# mm_controller_v1.net
KiCad netlist of a schematic drawn in EAGLE
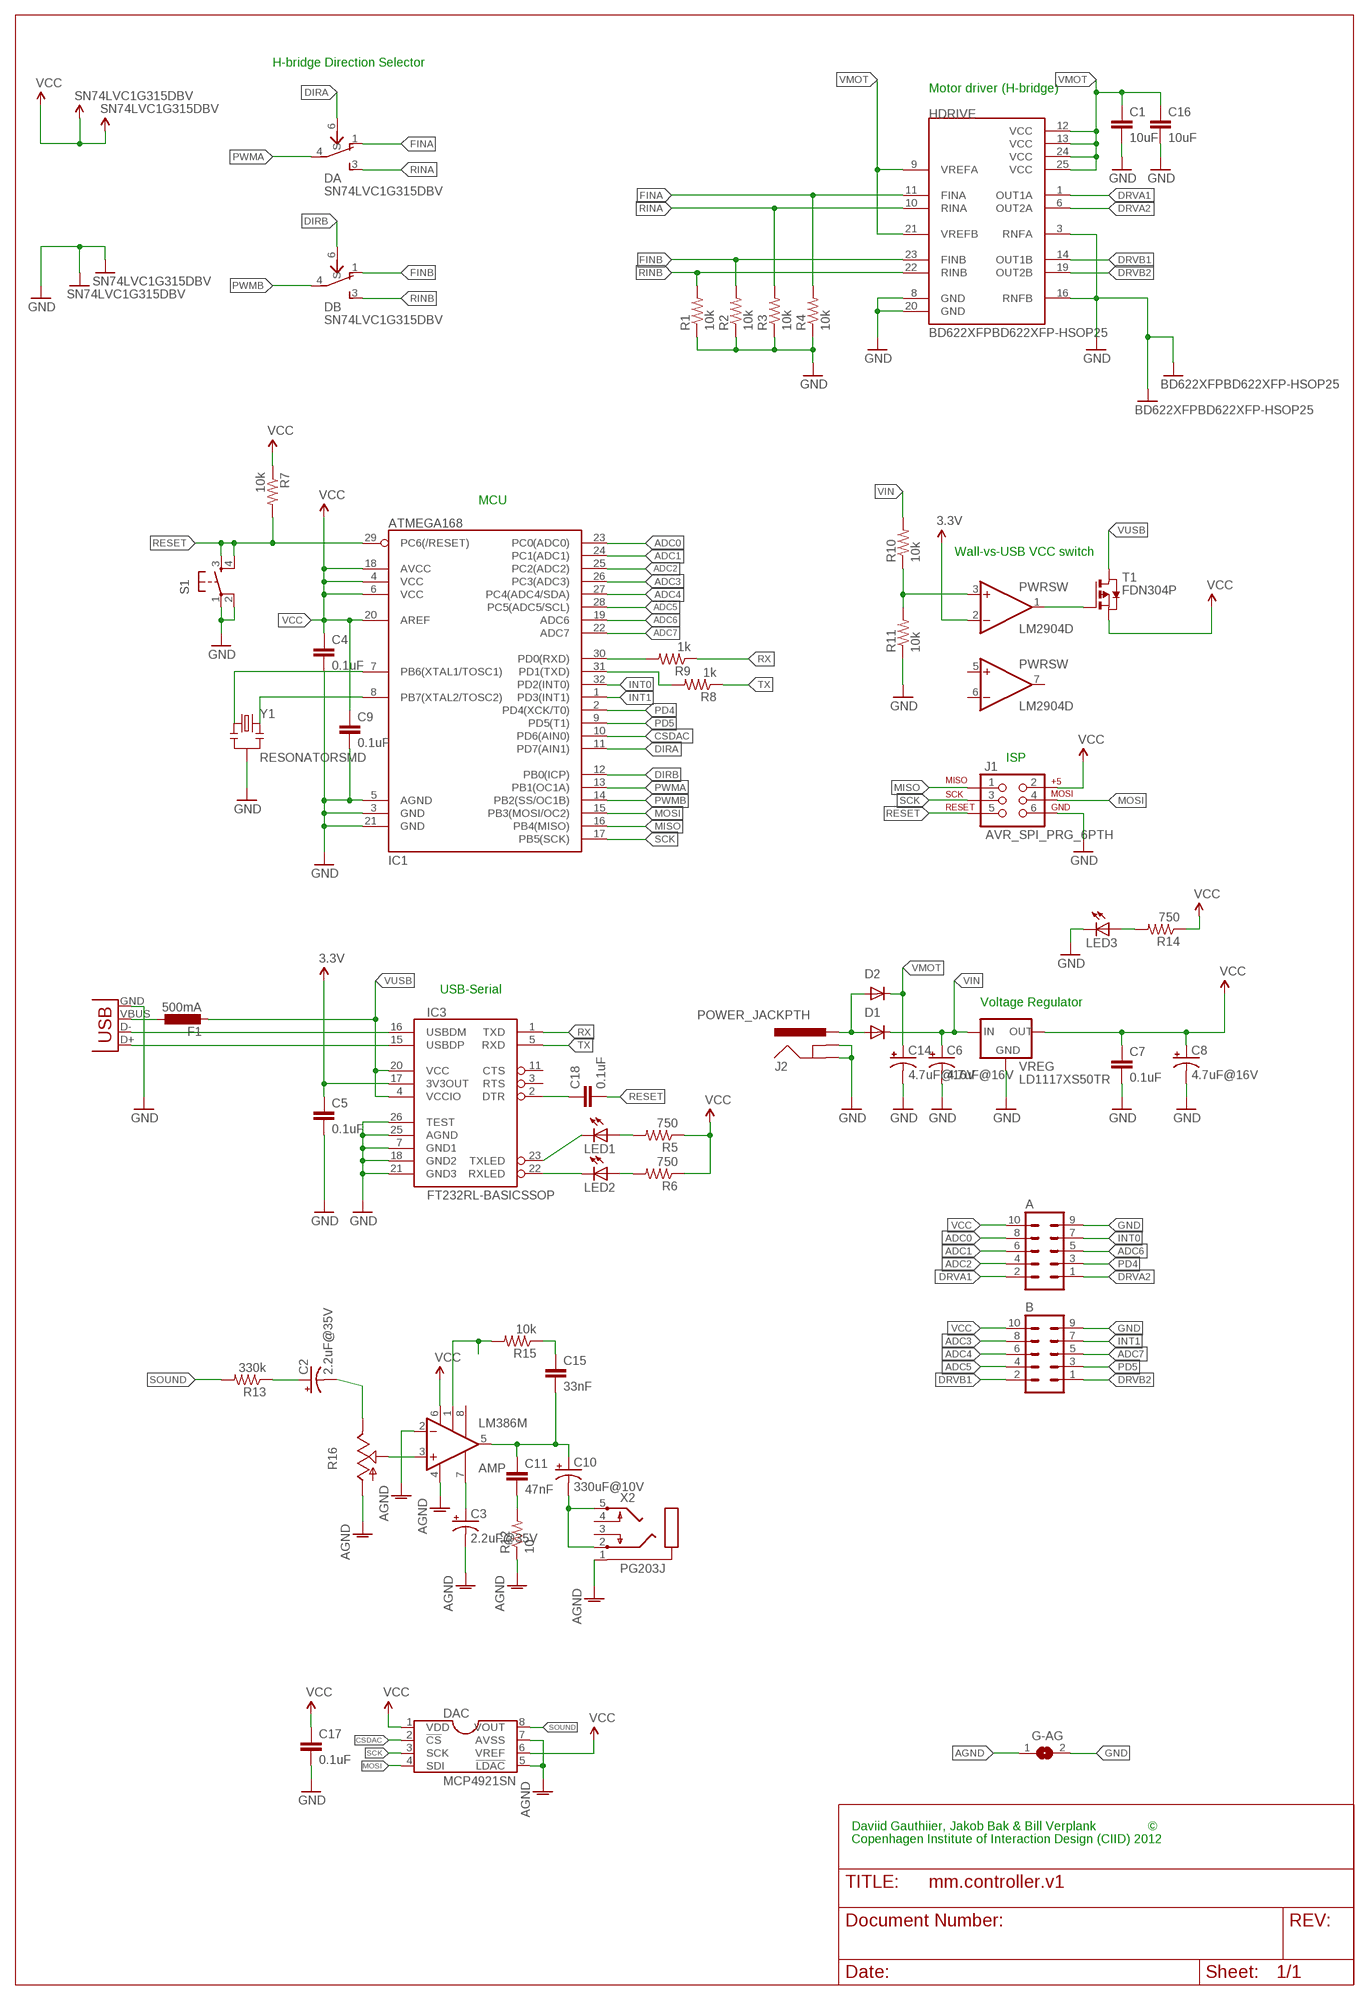
[diagram p0: schematic, sheet 1]

(export (version "E")
  (design (tool "Eeschema 10.0.6"))
  (components
    (comp (ref "A")
      (value "ML10")
      (footprint "eagle-import:ML10")
      (libsource (lib "eagle-import") (part "ML10"))
    )
    (comp (ref "AMP")
      (value "LM386M")
      (footprint "eagle-import:SOIC8")
      (libsource (lib "eagle-import") (part "LM386M"))
    )
    (comp (ref "B")
      (value "ML10")
      (footprint "eagle-import:ML10")
      (libsource (lib "eagle-import") (part "ML10"))
    )
    (comp (ref "C1")
      (value "10uF")
      (footprint "eagle-import:0805")
      (libsource (lib "eagle-import") (part "CAP0805"))
    )
    (comp (ref "C2")
      (value "2.2uF@35V")
      (footprint "eagle-import:PANASONIC_B")
      (libsource (lib "eagle-import") (part "CPOL-USB"))
    )
    (comp (ref "C3")
      (value "2.2uF@35V")
      (footprint "eagle-import:PANASONIC_B")
      (libsource (lib "eagle-import") (part "CPOL-USB"))
    )
    (comp (ref "C4")
      (value "0.1uF")
      (footprint "eagle-import:0805")
      (libsource (lib "eagle-import") (part "CAP0805"))
    )
    (comp (ref "C5")
      (value "0.1uF")
      (footprint "eagle-import:0805")
      (libsource (lib "eagle-import") (part "CAP0805"))
    )
    (comp (ref "C6")
      (value "4.7uF@16V")
      (footprint "eagle-import:PANASONIC_B")
      (libsource (lib "eagle-import") (part "CPOL-USB"))
    )
    (comp (ref "C7")
      (value "0.1uF")
      (footprint "eagle-import:0805")
      (libsource (lib "eagle-import") (part "CAP0805"))
    )
    (comp (ref "C8")
      (value "4.7uF@16V")
      (footprint "eagle-import:PANASONIC_B")
      (libsource (lib "eagle-import") (part "CPOL-USB"))
    )
    (comp (ref "C9")
      (value "0.1uF")
      (footprint "eagle-import:0805")
      (libsource (lib "eagle-import") (part "CAP0805"))
    )
    (comp (ref "C10")
      (value "330uF@10V")
      (footprint "eagle-import:PANASONIC_F")
      (libsource (lib "eagle-import") (part "CPOL-USF"))
    )
    (comp (ref "C11")
      (value "47nF")
      (footprint "eagle-import:0805")
      (libsource (lib "eagle-import") (part "CAP0805"))
    )
    (comp (ref "C14")
      (value "4.7uF@16V")
      (footprint "eagle-import:PANASONIC_B")
      (libsource (lib "eagle-import") (part "CPOL-USB"))
    )
    (comp (ref "C15")
      (value "33nF")
      (footprint "eagle-import:0805")
      (libsource (lib "eagle-import") (part "CAP0805"))
    )
    (comp (ref "C16")
      (value "10uF")
      (footprint "eagle-import:0805")
      (libsource (lib "eagle-import") (part "CAP0805"))
    )
    (comp (ref "C17")
      (value "0.1uF")
      (footprint "eagle-import:0805")
      (libsource (lib "eagle-import") (part "CAP0805"))
    )
    (comp (ref "C18")
      (value "0.1uF")
      (footprint "eagle-import:0805")
      (libsource (lib "eagle-import") (part "CAP0805"))
    )
    (comp (ref "D1")
      (value "DIODESMB")
      (footprint "eagle-import:SMB-DIODE")
      (libsource (lib "eagle-import") (part "DIODESMB"))
    )
    (comp (ref "D2")
      (value "DIODESMB")
      (footprint "eagle-import:SMB-DIODE")
      (libsource (lib "eagle-import") (part "DIODESMB"))
    )
    (comp (ref "DA")
      (value "SN74LVC1G315DBV")
      (footprint "eagle-import:SOT23-6")
      (libsource (lib "eagle-import") (part "SN74LVC1G315DBV"))
    )
    (comp (ref "DAC")
      (value "MCP4921SN")
      (footprint "eagle-import:SOIC8")
      (libsource (lib "eagle-import") (part "MCP4921SN"))
    )
    (comp (ref "DB")
      (value "SN74LVC1G315DBV")
      (footprint "eagle-import:SOT23-6")
      (libsource (lib "eagle-import") (part "SN74LVC1G315DBV"))
    )
    (comp (ref "F1")
      (value "500mA")
      (footprint "eagle-import:L1812")
      (libsource (lib "eagle-import") (part "L-EUL1812"))
    )
    (comp (ref "G-AG")
      (value "SJ")
      (footprint "eagle-import:SJ")
      (libsource (lib "eagle-import") (part "SJ"))
    )
    (comp (ref "HDRIVE")
      (value "BD622XFPBD622XFP-HSOP25")
      (footprint "eagle-import:HSOP25")
      (libsource (lib "eagle-import") (part "BD622XFPBD622XFP-HSOP25"))
    )
    (comp (ref "IC1")
      (value "ATMEGA168")
      (footprint "eagle-import:TQFP32-08")
      (libsource (lib "eagle-import") (part "ATMEGA168"))
    )
    (comp (ref "IC3")
      (value "FT232RL-BASICSSOP")
      (footprint "eagle-import:SSOP28DB")
      (libsource (lib "eagle-import") (part "FT232RL-BASICSSOP"))
    )
    (comp (ref "J1")
      (value "AVR_SPI_PRG_6PTH")
      (footprint "eagle-import:2X3")
      (libsource (lib "eagle-import") (part "AVR_SPI_PRG_6PTH"))
    )
    (comp (ref "J2")
      (value "POWER_JACKPTH")
      (footprint "eagle-import:POWER_JACK_PTH")
      (libsource (lib "eagle-import") (part "POWER_JACKPTH"))
    )
    (comp (ref "LED1")
      (value "LED1206")
      (footprint "eagle-import:LED-1206")
      (libsource (lib "eagle-import") (part "LED1206"))
    )
    (comp (ref "LED2")
      (value "LED1206")
      (footprint "eagle-import:LED-1206")
      (libsource (lib "eagle-import") (part "LED1206"))
    )
    (comp (ref "LED3")
      (value "LED1206")
      (footprint "eagle-import:LED-1206")
      (libsource (lib "eagle-import") (part "LED1206"))
    )
    (comp (ref "PWRSW")
      (value "LM2904D")
      (footprint "eagle-import:SOIC8")
      (libsource (lib "eagle-import") (part "LM2904D"))
    )
    (comp (ref "R1")
      (value "10k")
      (footprint "eagle-import:0805")
      (libsource (lib "eagle-import") (part "RESISTOR0805-RES"))
    )
    (comp (ref "R2")
      (value "10k")
      (footprint "eagle-import:0805")
      (libsource (lib "eagle-import") (part "RESISTOR0805-RES"))
    )
    (comp (ref "R3")
      (value "10k")
      (footprint "eagle-import:0805")
      (libsource (lib "eagle-import") (part "RESISTOR0805-RES"))
    )
    (comp (ref "R4")
      (value "10k")
      (footprint "eagle-import:0805")
      (libsource (lib "eagle-import") (part "RESISTOR0805-RES"))
    )
    (comp (ref "R5")
      (value "750")
      (footprint "eagle-import:0805")
      (libsource (lib "eagle-import") (part "RESISTOR0805-RES"))
    )
    (comp (ref "R6")
      (value "750")
      (footprint "eagle-import:0805")
      (libsource (lib "eagle-import") (part "RESISTOR0805-RES"))
    )
    (comp (ref "R7")
      (value "10k")
      (footprint "eagle-import:0805")
      (libsource (lib "eagle-import") (part "RESISTOR0805-RES"))
    )
    (comp (ref "R8")
      (value "1k")
      (footprint "eagle-import:0805")
      (libsource (lib "eagle-import") (part "RESISTOR0805-RES"))
    )
    (comp (ref "R9")
      (value "1k")
      (footprint "eagle-import:0805")
      (libsource (lib "eagle-import") (part "RESISTOR0805-RES"))
    )
    (comp (ref "R10")
      (value "10k")
      (footprint "eagle-import:0805")
      (libsource (lib "eagle-import") (part "RESISTOR0805-RES"))
    )
    (comp (ref "R11")
      (value "10k")
      (footprint "eagle-import:0805")
      (libsource (lib "eagle-import") (part "RESISTOR0805-RES"))
    )
    (comp (ref "R12")
      (value "10")
      (footprint "eagle-import:0805")
      (libsource (lib "eagle-import") (part "RESISTOR0805-RES"))
    )
    (comp (ref "R13")
      (value "330k")
      (footprint "eagle-import:0805")
      (libsource (lib "eagle-import") (part "RESISTOR0805-RES"))
    )
    (comp (ref "R14")
      (value "750")
      (footprint "eagle-import:0805")
      (libsource (lib "eagle-import") (part "RESISTOR0805-RES"))
    )
    (comp (ref "R15")
      (value "10k")
      (footprint "eagle-import:0805")
      (libsource (lib "eagle-import") (part "RESISTOR0805-RES"))
    )
    (comp (ref "R16")
      (value "TRIM_US-PT10")
      (footprint "eagle-import:PT-10")
      (libsource (lib "eagle-import") (part "TRIM_US-PT10"))
    )
    (comp (ref "S1")
      (value "TAC_SWITCHSMD")
      (footprint "eagle-import:TACTILE_SWITCH_SMD")
      (libsource (lib "eagle-import") (part "TAC_SWITCHSMD"))
    )
    (comp (ref "T1")
      (value "FDN304P")
      (footprint "eagle-import:SOT-23")
      (libsource (lib "eagle-import") (part "PMOSSOT23"))
    )
    (comp (ref "VREG")
      (value "LD1117XS50TR")
      (footprint "eagle-import:SOT223")
      (libsource (lib "eagle-import") (part "LD1117XS50TR"))
    )
    (comp (ref "X1")
      (value "USB-SMD-NS")
      (footprint "eagle-import:USB-MINIB-NOSTOP")
      (libsource (lib "eagle-import") (part "USB-SMD-NS"))
    )
    (comp (ref "X2")
      (value "PG203J")
      (footprint "eagle-import:PG203J")
      (libsource (lib "eagle-import") (part "PG203J"))
    )
    (comp (ref "Y1")
      (value "RESONATORSMD")
      (footprint "eagle-import:RESONATOR-SMD")
      (libsource (lib "eagle-import") (part "RESONATORSMD"))
    )
  )
  (nets
    (net (code "1") (name "3.3V") (class "Default")
      (node (ref "C5") (pin "1") (pinfunction "1_1") (pintype "passive"))
      (node (ref "IC3") (pin "17") (pinfunction "3V3OUT_17") (pintype "output"))
      (node (ref "PWRSW") (pin "2") (pinfunction "-INA_2") (pintype "input"))
    )
    (net (code "2") (name "ADC0") (class "Default")
      (node (ref "A") (pin "8") (pinfunction "8_8") (pintype "passive"))
      (node (ref "IC1") (pin "23") (pinfunction "PC0(ADC0)_23") (pintype "bidirectional"))
    )
    (net (code "3") (name "ADC1") (class "Default")
      (node (ref "A") (pin "6") (pinfunction "6_6") (pintype "passive"))
      (node (ref "IC1") (pin "24") (pinfunction "PC1(ADC1)_24") (pintype "bidirectional"))
    )
    (net (code "4") (name "ADC2") (class "Default")
      (node (ref "A") (pin "4") (pinfunction "4_4") (pintype "passive"))
      (node (ref "IC1") (pin "25") (pinfunction "PC2(ADC2)_25") (pintype "bidirectional"))
    )
    (net (code "5") (name "ADC3") (class "Default")
      (node (ref "B") (pin "8") (pinfunction "8_8") (pintype "passive"))
      (node (ref "IC1") (pin "26") (pinfunction "PC3(ADC3)_26") (pintype "bidirectional"))
    )
    (net (code "6") (name "ADC4") (class "Default")
      (node (ref "B") (pin "6") (pinfunction "6_6") (pintype "passive"))
      (node (ref "IC1") (pin "27") (pinfunction "PC4(ADC4/SDA)_27") (pintype "bidirectional"))
    )
    (net (code "7") (name "ADC5") (class "Default")
      (node (ref "B") (pin "4") (pinfunction "4_4") (pintype "passive"))
      (node (ref "IC1") (pin "28") (pinfunction "PC5(ADC5/SCL)_28") (pintype "bidirectional"))
    )
    (net (code "8") (name "ADC6") (class "Default")
      (node (ref "A") (pin "5") (pinfunction "5_5") (pintype "passive"))
      (node (ref "IC1") (pin "19") (pinfunction "ADC6_19") (pintype "bidirectional"))
    )
    (net (code "9") (name "ADC7") (class "Default")
      (node (ref "B") (pin "5") (pinfunction "5_5") (pintype "passive"))
      (node (ref "IC1") (pin "22") (pinfunction "ADC7_22") (pintype "bidirectional"))
    )
    (net (code "10") (name "AGND") (class "Default")
      (node (ref "AMP") (pin "2") (pinfunction "-IN_2") (pintype "input"))
      (node (ref "AMP") (pin "4") (pinfunction "V-_4") (pintype "power_in"))
      (node (ref "C3") (pin "-") (pinfunction "-_-") (pintype "passive"))
      (node (ref "DAC") (pin "5") (pinfunction "~{LDAC}_5") (pintype "input"))
      (node (ref "DAC") (pin "7") (pinfunction "AVSS_7") (pintype "power_in"))
      (node (ref "G-AG") (pin "1") (pinfunction "1_1") (pintype "passive"))
      (node (ref "R12") (pin "1") (pinfunction "1_1") (pintype "passive"))
      (node (ref "R16") (pin "A") (pinfunction "A_A") (pintype "passive"))
      (node (ref "X2") (pin "1") (pinfunction "1_1") (pintype "passive"))
    )
    (net (code "11") (name "CSDAC") (class "Default")
      (node (ref "DAC") (pin "2") (pinfunction "~{CS}_2") (pintype "input"))
      (node (ref "IC1") (pin "10") (pinfunction "PD6(AIN0)_10") (pintype "bidirectional"))
    )
    (net (code "12") (name "DIRA") (class "Default")
      (node (ref "DA") (pin "6") (pinfunction "S_6") (pintype "passive"))
      (node (ref "IC1") (pin "11") (pinfunction "PD7(AIN1)_11") (pintype "bidirectional"))
    )
    (net (code "13") (name "DIRB") (class "Default")
      (node (ref "DB") (pin "6") (pinfunction "S_6") (pintype "passive"))
      (node (ref "IC1") (pin "12") (pinfunction "PB0(ICP)_12") (pintype "bidirectional"))
    )
    (net (code "14") (name "DRVA1") (class "Default")
      (node (ref "A") (pin "2") (pinfunction "2_2") (pintype "passive"))
      (node (ref "HDRIVE") (pin "1") (pinfunction "OUT1A_1") (pintype "bidirectional"))
    )
    (net (code "15") (name "DRVA2") (class "Default")
      (node (ref "A") (pin "1") (pinfunction "1_1") (pintype "passive"))
      (node (ref "HDRIVE") (pin "6") (pinfunction "OUT2A_6") (pintype "bidirectional"))
    )
    (net (code "16") (name "DRVB1") (class "Default")
      (node (ref "B") (pin "2") (pinfunction "2_2") (pintype "passive"))
      (node (ref "HDRIVE") (pin "14") (pinfunction "OUT1B_14") (pintype "bidirectional"))
    )
    (net (code "17") (name "DRVB2") (class "Default")
      (node (ref "B") (pin "1") (pinfunction "1_1") (pintype "passive"))
      (node (ref "HDRIVE") (pin "19") (pinfunction "OUT2B_19") (pintype "bidirectional"))
    )
    (net (code "18") (name "FINA") (class "Default")
      (node (ref "DA") (pin "1") (pinfunction "INA_1") (pintype "passive"))
      (node (ref "HDRIVE") (pin "11") (pinfunction "FINA_11") (pintype "bidirectional"))
      (node (ref "R4") (pin "2") (pinfunction "2_2") (pintype "passive"))
    )
    (net (code "19") (name "FINB") (class "Default")
      (node (ref "DB") (pin "1") (pinfunction "INA_1") (pintype "passive"))
      (node (ref "HDRIVE") (pin "23") (pinfunction "FINB_23") (pintype "bidirectional"))
      (node (ref "R2") (pin "2") (pinfunction "2_2") (pintype "passive"))
    )
    (net (code "20") (name "GND") (class "Default")
      (node (ref "A") (pin "9") (pinfunction "9_9") (pintype "passive"))
      (node (ref "B") (pin "9") (pinfunction "9_9") (pintype "passive"))
      (node (ref "C1") (pin "2") (pinfunction "2_2") (pintype "passive"))
      (node (ref "C14") (pin "-") (pinfunction "-_-") (pintype "passive"))
      (node (ref "C16") (pin "2") (pinfunction "2_2") (pintype "passive"))
      (node (ref "C17") (pin "2") (pinfunction "2_2") (pintype "passive"))
      (node (ref "C4") (pin "2") (pinfunction "2_2") (pintype "passive"))
      (node (ref "C5") (pin "2") (pinfunction "2_2") (pintype "passive"))
      (node (ref "C6") (pin "-") (pinfunction "-_-") (pintype "passive"))
      (node (ref "C7") (pin "2") (pinfunction "2_2") (pintype "passive"))
      (node (ref "C8") (pin "-") (pinfunction "-_-") (pintype "passive"))
      (node (ref "C9") (pin "2") (pinfunction "2_2") (pintype "passive"))
      (node (ref "DA") (pin "2") (pinfunction "GND_2") (pintype "power_in"))
      (node (ref "DB") (pin "2") (pinfunction "GND_2") (pintype "power_in"))
      (node (ref "G-AG") (pin "2") (pinfunction "2_2") (pintype "passive"))
      (node (ref "HDRIVE") (pin "16") (pinfunction "RNFB_16") (pintype "bidirectional"))
      (node (ref "HDRIVE") (pin "20") (pinfunction "GND_20") (pintype "power_in"))
      (node (ref "HDRIVE") (pin "3") (pinfunction "RNFA_3") (pintype "bidirectional"))
      (node (ref "HDRIVE") (pin "8") (pinfunction "GND_8") (pintype "power_in"))
      (node (ref "HDRIVE") (pin "GND@1") (pinfunction "GND_GND@1") (pintype "power_in"))
      (node (ref "HDRIVE") (pin "GND@2") (pinfunction "GND_GND@2") (pintype "power_in"))
      (node (ref "IC1") (pin "21") (pinfunction "GND_21") (pintype "bidirectional"))
      (node (ref "IC1") (pin "3") (pinfunction "GND_3") (pintype "bidirectional"))
      (node (ref "IC1") (pin "5") (pinfunction "AGND_5") (pintype "bidirectional"))
      (node (ref "IC3") (pin "18") (pinfunction "GND2_18") (pintype "power_in"))
      (node (ref "IC3") (pin "21") (pinfunction "GND3_21") (pintype "power_in"))
      (node (ref "IC3") (pin "25") (pinfunction "AGND_25") (pintype "power_in"))
      (node (ref "IC3") (pin "26") (pinfunction "TEST_26") (pintype "input"))
      (node (ref "IC3") (pin "7") (pinfunction "GND1_7") (pintype "power_in"))
      (node (ref "J1") (pin "6") (pinfunction "6_6") (pintype "passive"))
      (node (ref "J2") (pin "GND") (pinfunction "GND_GND") (pintype "bidirectional"))
      (node (ref "J2") (pin "GNDBREAK") (pinfunction "GNDBREAK_GNDBREAK") (pintype "bidirectional"))
      (node (ref "LED3") (pin "C") (pinfunction "C_C") (pintype "passive"))
      (node (ref "R1") (pin "1") (pinfunction "1_1") (pintype "passive"))
      (node (ref "R11") (pin "1") (pinfunction "1_1") (pintype "passive"))
      (node (ref "R2") (pin "1") (pinfunction "1_1") (pintype "passive"))
      (node (ref "R3") (pin "1") (pinfunction "1_1") (pintype "passive"))
      (node (ref "R4") (pin "1") (pinfunction "1_1") (pintype "passive"))
      (node (ref "S1") (pin "1") (pinfunction "1_1") (pintype "passive"))
      (node (ref "S1") (pin "2") (pinfunction "2_2") (pintype "passive"))
      (node (ref "VREG") (pin "1") (pinfunction "GND_1") (pintype "input"))
      (node (ref "X1") (pin "GND") (pinfunction "GND_GND") (pintype "bidirectional"))
      (node (ref "Y1") (pin "2") (pinfunction "2_2") (pintype "passive"))
    )
    (net (code "21") (name "INT0") (class "Default")
      (node (ref "A") (pin "7") (pinfunction "7_7") (pintype "passive"))
      (node (ref "IC1") (pin "32") (pinfunction "PD2(INT0)_32") (pintype "bidirectional"))
    )
    (net (code "22") (name "INT1") (class "Default")
      (node (ref "B") (pin "7") (pinfunction "7_7") (pintype "passive"))
      (node (ref "IC1") (pin "1") (pinfunction "PD3(INT1)_1") (pintype "bidirectional"))
    )
    (net (code "23") (name "MISO") (class "Default")
      (node (ref "IC1") (pin "16") (pinfunction "PB4(MISO)_16") (pintype "bidirectional"))
      (node (ref "J1") (pin "1") (pinfunction "1_1") (pintype "passive"))
    )
    (net (code "24") (name "MOSI") (class "Default")
      (node (ref "DAC") (pin "4") (pinfunction "SDI_4") (pintype "input"))
      (node (ref "IC1") (pin "15") (pinfunction "PB3(MOSI/OC2)_15") (pintype "bidirectional"))
      (node (ref "J1") (pin "4") (pinfunction "4_4") (pintype "passive"))
    )
    (net (code "25") (name "Net-(AMP-+IN)") (class "Default")
      (node (ref "AMP") (pin "3") (pinfunction "+IN_3") (pintype "input"))
      (node (ref "R16") (pin "S") (pinfunction "S_S") (pintype "passive"))
    )
    (net (code "26") (name "Net-(AMP-BYPASS)") (class "Default")
      (node (ref "AMP") (pin "7") (pinfunction "BYPASS_7") (pintype "passive"))
      (node (ref "C3") (pin "+") (pinfunction "+_+") (pintype "passive"))
    )
    (net (code "27") (name "Net-(AMP-G1)") (class "Default")
      (node (ref "AMP") (pin "1") (pinfunction "G1_1") (pintype "passive"))
      (node (ref "R15") (pin "2") (pinfunction "2_2") (pintype "passive"))
    )
    (net (code "28") (name "Net-(AMP-OUT)") (class "Default")
      (node (ref "AMP") (pin "5") (pinfunction "OUT_5") (pintype "output"))
      (node (ref "C10") (pin "+") (pinfunction "+_+") (pintype "passive"))
      (node (ref "C11") (pin "1") (pinfunction "1_1") (pintype "passive"))
      (node (ref "C15") (pin "2") (pinfunction "2_2") (pintype "passive"))
    )
    (net (code "29") (name "Net-(C2-Pad+)") (class "Default")
      (node (ref "C2") (pin "+") (pinfunction "+_+") (pintype "passive"))
      (node (ref "R13") (pin "1") (pinfunction "1_1") (pintype "passive"))
    )
    (net (code "30") (name "Net-(C2-Pad-)") (class "Default")
      (node (ref "C2") (pin "-") (pinfunction "-_-") (pintype "passive"))
      (node (ref "R16") (pin "E") (pinfunction "E_E") (pintype "passive"))
    )
    (net (code "31") (name "Net-(C10-Pad-)") (class "Default")
      (node (ref "C10") (pin "-") (pinfunction "-_-") (pintype "passive"))
      (node (ref "X2") (pin "2") (pinfunction "2_2") (pintype "passive"))
      (node (ref "X2") (pin "5") (pinfunction "5_5") (pintype "passive"))
    )
    (net (code "32") (name "Net-(C11-Pad2)") (class "Default")
      (node (ref "C11") (pin "2") (pinfunction "2_2") (pintype "passive"))
      (node (ref "R12") (pin "2") (pinfunction "2_2") (pintype "passive"))
    )
    (net (code "33") (name "Net-(C15-Pad1)") (class "Default")
      (node (ref "C15") (pin "1") (pinfunction "1_1") (pintype "passive"))
      (node (ref "R15") (pin "1") (pinfunction "1_1") (pintype "passive"))
    )
    (net (code "34") (name "Net-(D1-PadA)") (class "Default")
      (node (ref "D1") (pin "A") (pinfunction "A_A") (pintype "passive"))
      (node (ref "D2") (pin "A") (pinfunction "A_A") (pintype "passive"))
      (node (ref "J2") (pin "PWR") (pinfunction "PWR_PWR") (pintype "bidirectional"))
    )
    (net (code "35") (name "Net-(F1-Pad1)") (class "Default")
      (node (ref "F1") (pin "1") (pinfunction "1_1") (pintype "passive"))
      (node (ref "X1") (pin "VBUS") (pinfunction "VBUS_VBUS") (pintype "bidirectional"))
    )
    (net (code "36") (name "Net-(IC1-PB6(XTAL1{slash}TOSC1))") (class "Default")
      (node (ref "IC1") (pin "7") (pinfunction "PB6(XTAL1/TOSC1)_7") (pintype "bidirectional"))
      (node (ref "Y1") (pin "1") (pinfunction "1_1") (pintype "passive"))
    )
    (net (code "37") (name "Net-(IC1-PB7(XTAL2{slash}TOSC2))") (class "Default")
      (node (ref "IC1") (pin "8") (pinfunction "PB7(XTAL2/TOSC2)_8") (pintype "bidirectional"))
      (node (ref "Y1") (pin "3") (pinfunction "3_3") (pintype "passive"))
    )
    (net (code "38") (name "Net-(IC1-PD0(RXD))") (class "Default")
      (node (ref "IC1") (pin "30") (pinfunction "PD0(RXD)_30") (pintype "bidirectional"))
      (node (ref "R9") (pin "2") (pinfunction "2_2") (pintype "passive"))
    )
    (net (code "39") (name "Net-(IC1-PD1(TXD))") (class "Default")
      (node (ref "IC1") (pin "31") (pinfunction "PD1(TXD)_31") (pintype "bidirectional"))
      (node (ref "R8") (pin "2") (pinfunction "2_2") (pintype "passive"))
    )
    (net (code "40") (name "Net-(IC3-DTR)") (class "Default")
      (node (ref "C18") (pin "1") (pinfunction "1_1") (pintype "passive"))
      (node (ref "IC3") (pin "2") (pinfunction "DTR_2") (pintype "bidirectional"))
    )
    (net (code "41") (name "Net-(IC3-RXLED)") (class "Default")
      (node (ref "IC3") (pin "22") (pinfunction "RXLED_22") (pintype "bidirectional"))
      (node (ref "LED2") (pin "C") (pinfunction "C_C") (pintype "passive"))
    )
    (net (code "42") (name "Net-(IC3-TXLED)") (class "Default")
      (node (ref "IC3") (pin "23") (pinfunction "TXLED_23") (pintype "bidirectional"))
      (node (ref "LED1") (pin "C") (pinfunction "C_C") (pintype "passive"))
    )
    (net (code "43") (name "Net-(IC3-USBDM)") (class "Default")
      (node (ref "IC3") (pin "16") (pinfunction "USBDM_16") (pintype "bidirectional"))
      (node (ref "X1") (pin "D-") (pinfunction "D-_D-") (pintype "bidirectional"))
    )
    (net (code "44") (name "Net-(IC3-USBDP)") (class "Default")
      (node (ref "IC3") (pin "15") (pinfunction "USBDP_15") (pintype "bidirectional"))
      (node (ref "X1") (pin "D+") (pinfunction "D+_D+") (pintype "bidirectional"))
    )
    (net (code "45") (name "Net-(LED1-PadA)") (class "Default")
      (node (ref "LED1") (pin "A") (pinfunction "A_A") (pintype "passive"))
      (node (ref "R5") (pin "2") (pinfunction "2_2") (pintype "passive"))
    )
    (net (code "46") (name "Net-(LED2-PadA)") (class "Default")
      (node (ref "LED2") (pin "A") (pinfunction "A_A") (pintype "passive"))
      (node (ref "R6") (pin "2") (pinfunction "2_2") (pintype "passive"))
    )
    (net (code "47") (name "Net-(LED3-PadA)") (class "Default")
      (node (ref "LED3") (pin "A") (pinfunction "A_A") (pintype "passive"))
      (node (ref "R14") (pin "2") (pinfunction "2_2") (pintype "passive"))
    )
    (net (code "48") (name "Net-(PWRSWA-+INA)") (class "Default")
      (node (ref "PWRSW") (pin "3") (pinfunction "+INA_3") (pintype "input"))
      (node (ref "R10") (pin "1") (pinfunction "1_1") (pintype "passive"))
      (node (ref "R11") (pin "2") (pinfunction "2_2") (pintype "passive"))
    )
    (net (code "49") (name "Net-(PWRSWA-OUTA)") (class "Default")
      (node (ref "PWRSW") (pin "1") (pinfunction "OUTA_1") (pintype "output"))
      (node (ref "T1") (pin "3") (pinfunction "G_3") (pintype "passive"))
    )
    (net (code "50") (name "PD4") (class "Default")
      (node (ref "A") (pin "3") (pinfunction "3_3") (pintype "passive"))
      (node (ref "IC1") (pin "2") (pinfunction "PD4(XCK/T0)_2") (pintype "bidirectional"))
    )
    (net (code "51") (name "PD5") (class "Default")
      (node (ref "B") (pin "3") (pinfunction "3_3") (pintype "passive"))
      (node (ref "IC1") (pin "9") (pinfunction "PD5(T1)_9") (pintype "bidirectional"))
    )
    (net (code "52") (name "PWMA") (class "Default")
      (node (ref "DA") (pin "4") (pinfunction "OUT_4") (pintype "passive"))
      (node (ref "IC1") (pin "13") (pinfunction "PB1(OC1A)_13") (pintype "bidirectional"))
    )
    (net (code "53") (name "PWMB") (class "Default")
      (node (ref "DB") (pin "4") (pinfunction "OUT_4") (pintype "passive"))
      (node (ref "IC1") (pin "14") (pinfunction "PB2(SS/OC1B)_14") (pintype "bidirectional"))
    )
    (net (code "54") (name "RESET") (class "Default")
      (node (ref "C18") (pin "2") (pinfunction "2_2") (pintype "passive"))
      (node (ref "IC1") (pin "29") (pinfunction "PC6(/RESET)_29") (pintype "bidirectional"))
      (node (ref "J1") (pin "5") (pinfunction "5_5") (pintype "passive"))
      (node (ref "R7") (pin "2") (pinfunction "2_2") (pintype "passive"))
      (node (ref "S1") (pin "3") (pinfunction "3_3") (pintype "passive"))
      (node (ref "S1") (pin "4") (pinfunction "4_4") (pintype "passive"))
    )
    (net (code "55") (name "RINA") (class "Default")
      (node (ref "DA") (pin "3") (pinfunction "INB_3") (pintype "passive"))
      (node (ref "HDRIVE") (pin "10") (pinfunction "RINA_10") (pintype "bidirectional"))
      (node (ref "R3") (pin "2") (pinfunction "2_2") (pintype "passive"))
    )
    (net (code "56") (name "RINB") (class "Default")
      (node (ref "DB") (pin "3") (pinfunction "INB_3") (pintype "passive"))
      (node (ref "HDRIVE") (pin "22") (pinfunction "RINB_22") (pintype "bidirectional"))
      (node (ref "R1") (pin "2") (pinfunction "2_2") (pintype "passive"))
    )
    (net (code "57") (name "RX") (class "Default")
      (node (ref "IC3") (pin "1") (pinfunction "TXD_1") (pintype "output"))
      (node (ref "R9") (pin "1") (pinfunction "1_1") (pintype "passive"))
    )
    (net (code "58") (name "SCK") (class "Default")
      (node (ref "DAC") (pin "3") (pinfunction "SCK_3") (pintype "input"))
      (node (ref "IC1") (pin "17") (pinfunction "PB5(SCK)_17") (pintype "bidirectional"))
      (node (ref "J1") (pin "3") (pinfunction "3_3") (pintype "passive"))
    )
    (net (code "59") (name "SOUND") (class "Default")
      (node (ref "DAC") (pin "8") (pinfunction "VOUT_8") (pintype "passive"))
      (node (ref "R13") (pin "2") (pinfunction "2_2") (pintype "passive"))
    )
    (net (code "60") (name "TX") (class "Default")
      (node (ref "IC3") (pin "5") (pinfunction "RXD_5") (pintype "input"))
      (node (ref "R8") (pin "1") (pinfunction "1_1") (pintype "passive"))
    )
    (net (code "61") (name "VCC") (class "Default")
      (node (ref "A") (pin "10") (pinfunction "10_10") (pintype "passive"))
      (node (ref "AMP") (pin "6") (pinfunction "V+_6") (pintype "power_in"))
      (node (ref "B") (pin "10") (pinfunction "10_10") (pintype "passive"))
      (node (ref "C17") (pin "1") (pinfunction "1_1") (pintype "passive"))
      (node (ref "C4") (pin "1") (pinfunction "1_1") (pintype "passive"))
      (node (ref "C7") (pin "1") (pinfunction "1_1") (pintype "passive"))
      (node (ref "C8") (pin "+") (pinfunction "+_+") (pintype "passive"))
      (node (ref "C9") (pin "1") (pinfunction "1_1") (pintype "passive"))
      (node (ref "DA") (pin "5") (pinfunction "VCC_5") (pintype "power_in"))
      (node (ref "DAC") (pin "1") (pinfunction "VDD_1") (pintype "power_in"))
      (node (ref "DAC") (pin "6") (pinfunction "VREF_6") (pintype "power_in"))
      (node (ref "DB") (pin "5") (pinfunction "VCC_5") (pintype "power_in"))
      (node (ref "IC1") (pin "18") (pinfunction "AVCC_18") (pintype "bidirectional"))
      (node (ref "IC1") (pin "20") (pinfunction "AREF_20") (pintype "bidirectional"))
      (node (ref "IC1") (pin "4") (pinfunction "VCC_4") (pintype "bidirectional"))
      (node (ref "IC1") (pin "6") (pinfunction "VCC_6") (pintype "bidirectional"))
      (node (ref "J1") (pin "2") (pinfunction "2_2") (pintype "passive"))
      (node (ref "R14") (pin "1") (pinfunction "1_1") (pintype "passive"))
      (node (ref "R5") (pin "1") (pinfunction "1_1") (pintype "passive"))
      (node (ref "R6") (pin "1") (pinfunction "1_1") (pintype "passive"))
      (node (ref "R7") (pin "1") (pinfunction "1_1") (pintype "passive"))
      (node (ref "T1") (pin "2") (pinfunction "S_2") (pintype "passive"))
      (node (ref "VREG") (pin "2") (pinfunction "OUT_2") (pintype "passive"))
    )
    (net (code "62") (name "VIN") (class "Default")
      (node (ref "C6") (pin "+") (pinfunction "+_+") (pintype "passive"))
      (node (ref "D1") (pin "C") (pinfunction "C_C") (pintype "passive"))
      (node (ref "R10") (pin "2") (pinfunction "2_2") (pintype "passive"))
      (node (ref "VREG") (pin "3") (pinfunction "IN_3") (pintype "input"))
    )
    (net (code "63") (name "VMOT") (class "Default")
      (node (ref "C1") (pin "1") (pinfunction "1_1") (pintype "passive"))
      (node (ref "C14") (pin "+") (pinfunction "+_+") (pintype "passive"))
      (node (ref "C16") (pin "1") (pinfunction "1_1") (pintype "passive"))
      (node (ref "D2") (pin "C") (pinfunction "C_C") (pintype "passive"))
      (node (ref "HDRIVE") (pin "12") (pinfunction "VCC_12") (pintype "power_in"))
      (node (ref "HDRIVE") (pin "13") (pinfunction "VCC_13") (pintype "power_in"))
      (node (ref "HDRIVE") (pin "21") (pinfunction "VREFB_21") (pintype "power_in"))
      (node (ref "HDRIVE") (pin "24") (pinfunction "VCC_24") (pintype "power_in"))
      (node (ref "HDRIVE") (pin "25") (pinfunction "VCC_25") (pintype "power_in"))
      (node (ref "HDRIVE") (pin "9") (pinfunction "VREFA_9") (pintype "power_in"))
    )
    (net (code "64") (name "VUSB") (class "Default")
      (node (ref "F1") (pin "2") (pinfunction "2_2") (pintype "passive"))
      (node (ref "IC3") (pin "20") (pinfunction "VCC_20") (pintype "power_in"))
      (node (ref "IC3") (pin "4") (pinfunction "VCCIO_4") (pintype "power_in"))
      (node (ref "T1") (pin "1") (pinfunction "D_1") (pintype "passive"))
    )
    (net (code "65") (name "unconnected-(AMP-G2-Pad8)") (class "Default")
      (node (ref "AMP") (pin "8") (pinfunction "G2_8") (pintype "passive"))
    )
    (net (code "66") (name "unconnected-(IC3-CTS-Pad11)") (class "Default")
      (node (ref "IC3") (pin "11") (pinfunction "CTS_11") (pintype "bidirectional"))
    )
    (net (code "67") (name "unconnected-(IC3-RTS-Pad3)") (class "Default")
      (node (ref "IC3") (pin "3") (pinfunction "RTS_3") (pintype "bidirectional"))
    )
    (net (code "68") (name "unconnected-(PWRSWA-+INB-Pad5)") (class "Default")
      (node (ref "PWRSW") (pin "5") (pinfunction "+INB_5") (pintype "input"))
    )
    (net (code "69") (name "unconnected-(PWRSWA--INB-Pad6)") (class "Default")
      (node (ref "PWRSW") (pin "6") (pinfunction "-INB_6") (pintype "input"))
    )
    (net (code "70") (name "unconnected-(PWRSWA-OUTB-Pad7)") (class "Default")
      (node (ref "PWRSW") (pin "7") (pinfunction "OUTB_7") (pintype "output"))
    )
    (net (code "71") (name "unconnected-(X2-Pad3)") (class "Default")
      (node (ref "X2") (pin "3") (pinfunction "3_3") (pintype "passive"))
    )
    (net (code "72") (name "unconnected-(X2-Pad4)") (class "Default")
      (node (ref "X2") (pin "4") (pinfunction "4_4") (pintype "passive"))
    )
  )
)
